# P1.net
KiCad netlist of a schematic drawn in Altium Designer
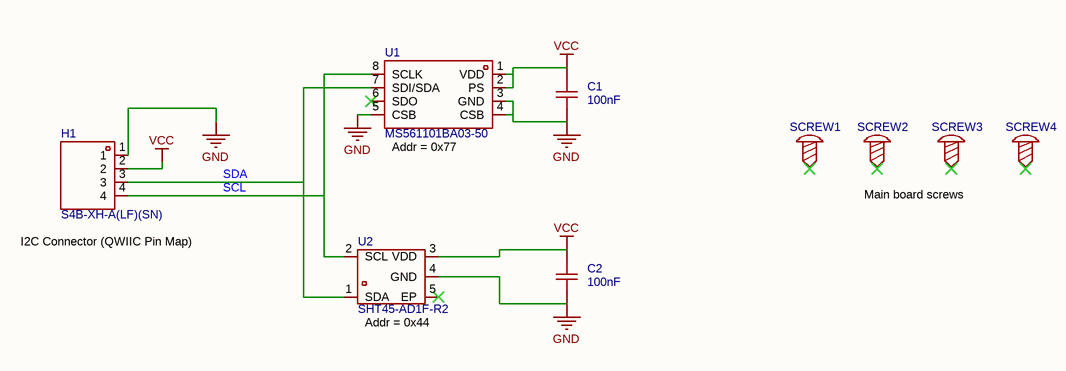
[diagram p0: P1.schdoc]

(export (version "E")
  (design (tool "Eeschema 10.0.6"))
  (components
    (comp (ref "C1")
      (value "100nF")
      (footprint "C0402")
      (description "Capacitance:100nF Tolerance:±10% Tolerance:±10% Voltage Rating:16V Temperature Coefficient:X7R")
      (fields (field (name "MANUFACTURER") "SAMSUNG(三星)") (field (name "MANUFACTURERPART") "CL05B104KO5NNNC"))
      (libsource (lib "altium-import") (part "root_1_CL05B104KO5NNNC_"))
    )
    (comp (ref "C2")
      (value "100nF")
      (footprint "C0402")
      (description "Capacitance:100nF Tolerance:±10% Tolerance:±10% Voltage Rating:16V Temperature Coefficient:X7R")
      (fields (field (name "MANUFACTURER") "SAMSUNG(三星)") (field (name "MANUFACTURERPART") "CL05B104KO5NNNC"))
      (libsource (lib "altium-import") (part "root_1_CL05B104KO5NNNC_"))
    )
    (comp (ref "H1")
      (value "S4B-XH-A(LF)(SN)")
      (footprint "CONN-TH_S4B-XH-A-LF-SN")
      (fields (field (name "MANUFACTURER") "JST"))
      (libsource (lib "altium-import") (part "root_0_mirrored_S4B-XH-A(LF)(SN)_"))
    )
    (comp (ref "SCREW1")
      (value "~")
      (footprint "Screw-Hole-M3")
      (libsource (lib "altium-import") (part "root_0_Screw-Hole-M3_"))
    )
    (comp (ref "SCREW2")
      (value "~")
      (footprint "Screw-Hole-M3")
      (libsource (lib "altium-import") (part "root_0_Screw-Hole-M3_"))
    )
    (comp (ref "SCREW3")
      (value "~")
      (footprint "Screw-Hole-M3")
      (libsource (lib "altium-import") (part "root_0_Screw-Hole-M3_"))
    )
    (comp (ref "SCREW4")
      (value "~")
      (footprint "Screw-Hole-M3")
      (libsource (lib "altium-import") (part "root_0_Screw-Hole-M3_"))
    )
    (comp (ref "U1")
      (value "MS561101BA03-50")
      (footprint "SENSORS-SMD_MS5611-01BA03")
      (fields (field (name "MANUFACTURER") "TE Connectivity(泰科电子)"))
      (libsource (lib "altium-import") (part "root_0_mirrored_MS561101BA03-50_"))
    )
    (comp (ref "U2")
      (value "SHT45-AD1F-R2")
      (footprint "DFN-4_L1.5-W1.5-P0.8-TL-EP")
      (fields (field (name "MANUFACTURER") "Sensirion(瑞士盛思锐)"))
      (libsource (lib "altium-import") (part "root_2_mirrored_SHT45-AD1F-R2_"))
    )
  )
  (nets
    (net (code "1") (name "/SCL") (class "Default")
      (node (ref "H1") (pin "4") (pinfunction "4_4") (pintype "passive"))
      (node (ref "U1") (pin "8") (pinfunction "SCLK_8") (pintype "passive"))
      (node (ref "U2") (pin "2") (pinfunction "SCL_2") (pintype "passive"))
    )
    (net (code "2") (name "/SDA") (class "Default")
      (node (ref "H1") (pin "3") (pinfunction "3_3") (pintype "passive"))
      (node (ref "U1") (pin "7") (pinfunction "SDI/SDA_7") (pintype "passive"))
      (node (ref "U2") (pin "1") (pinfunction "SDA_1") (pintype "passive"))
    )
    (net (code "3") (name "GND") (class "Default")
      (node (ref "C1") (pin "2") (pinfunction "2_2") (pintype "passive"))
      (node (ref "C2") (pin "2") (pinfunction "2_2") (pintype "passive"))
      (node (ref "H1") (pin "1") (pinfunction "1_1") (pintype "passive"))
      (node (ref "U1") (pin "3") (pinfunction "GND_3") (pintype "passive"))
      (node (ref "U1") (pin "4") (pinfunction "CSB_4") (pintype "passive"))
      (node (ref "U1") (pin "5") (pinfunction "CSB_5") (pintype "passive"))
      (node (ref "U2") (pin "4") (pinfunction "GND_4") (pintype "passive"))
    )
    (net (code "4") (name "VCC") (class "Default")
      (node (ref "C1") (pin "1") (pinfunction "1_1") (pintype "passive"))
      (node (ref "C2") (pin "1") (pinfunction "1_1") (pintype "passive"))
      (node (ref "H1") (pin "2") (pinfunction "2_2") (pintype "passive"))
      (node (ref "U1") (pin "1") (pinfunction "VDD_1") (pintype "passive"))
      (node (ref "U1") (pin "2") (pinfunction "PS_2") (pintype "passive"))
      (node (ref "U2") (pin "3") (pinfunction "VDD_3") (pintype "passive"))
    )
    (net (code "5") (name "unconnected-(SCREW1-Pad1)") (class "Default")
      (node (ref "SCREW1") (pin "1") (pinfunction "1_1") (pintype "passive+no_connect"))
    )
    (net (code "6") (name "unconnected-(SCREW2-Pad1)") (class "Default")
      (node (ref "SCREW2") (pin "1") (pinfunction "1_1") (pintype "passive+no_connect"))
    )
    (net (code "7") (name "unconnected-(SCREW3-Pad1)") (class "Default")
      (node (ref "SCREW3") (pin "1") (pinfunction "1_1") (pintype "passive+no_connect"))
    )
    (net (code "8") (name "unconnected-(SCREW4-Pad1)") (class "Default")
      (node (ref "SCREW4") (pin "1") (pinfunction "1_1") (pintype "passive+no_connect"))
    )
    (net (code "9") (name "unconnected-(U1-SDO-Pad6)") (class "Default")
      (node (ref "U1") (pin "6") (pinfunction "SDO_6") (pintype "passive+no_connect"))
    )
    (net (code "10") (name "unconnected-(U2-EP-Pad5)") (class "Default")
      (node (ref "U2") (pin "5") (pinfunction "EP_5") (pintype "passive+no_connect"))
    )
  )
)
